# WPT_Transmitter.net
KiCad netlist of a schematic drawn in Altium Designer
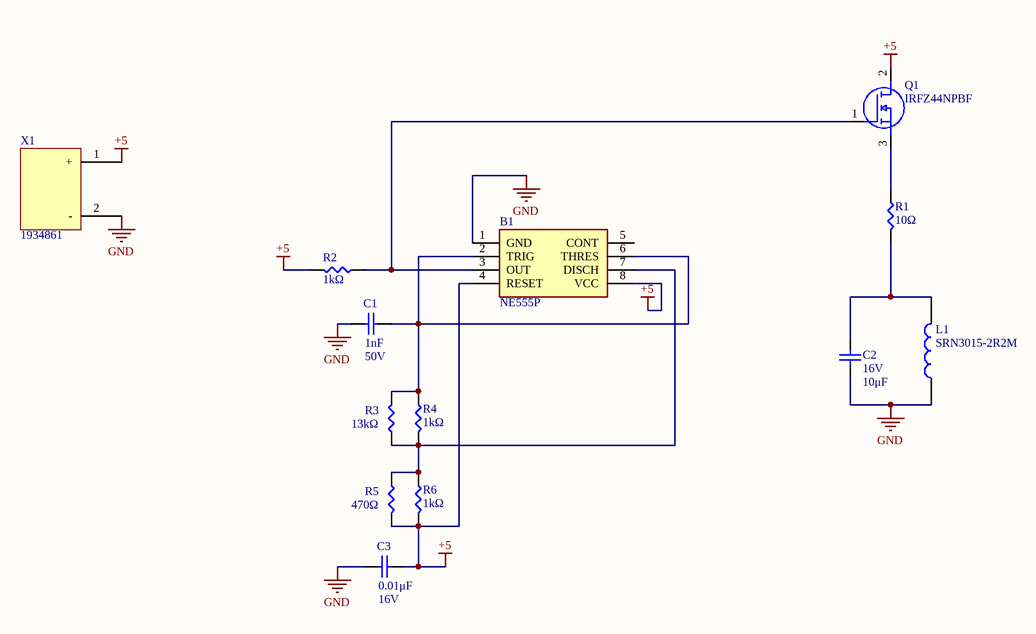
[diagram p0: WPT_Transmitter.SchDoc]

(export (version "E")
  (design (tool "Eeschema 10.0.6"))
  (components
    (comp (ref "B1")
      (value "NE555P")
      (footprint "DIP794W53P254L959H508Q8N")
      (fields (field (name "MOUSER PART NUMBER") "595-NE555P"))
      (libsource (lib "Bootcamp_Schematic_Library") (part "NE555P_1"))
    )
    (comp (ref "C1")
      (value "1nF")
      (footprint "CAP0805")
      (description "CAP CER 1000PF 50V C0G/NP0 0402")
      (fields (field (name "VOLTAGE RATING") "50V") (field (name "Comment") "GRM1555C1H102JA01D"))
      (libsource (lib "Bootcamp_Schematic_Library") (part "GRM1555C1H102JA01D"))
    )
    (comp (ref "C2")
      (value "10μF")
      (footprint "CAP0805")
      (description "CAP CER 10UF 16V X5R 0805")
      (fields (field (name "VOLTAGE RATING") "16V") (field (name "Comment") "CL21A106KOCLRNC"))
      (libsource (lib "Bootcamp_Schematic_Library") (part "CL21A106KOCLRNC"))
    )
    (comp (ref "C3")
      (value "0.01μF")
      (footprint "CAP0402")
      (description "CAP CER 10000PF 16V X7R 0402")
      (fields (field (name "VOLTAGE RATING") "16V") (field (name "Comment") "KGM05AR71C103KH"))
      (libsource (lib "Bootcamp_Schematic_Library") (part "KGM05AR71C103KH"))
    )
    (comp (ref "L1")
      (value "SRN3015-2R2M")
      (footprint "INDPM3027X150N")
      (fields (field (name "MOUSER PART NUMBER") "652-SRN3015-2R2M"))
      (libsource (lib "Bootcamp_Schematic_Library") (part "SRN3015-2R2M"))
    )
    (comp (ref "Q1")
      (value "IRFZ44NPBF")
      (footprint "TO254P483X1016X1994-3P")
      (fields (field (name "MOUSER PART NUMBER") "942-IRFZ44NPBF"))
      (libsource (lib "Bootcamp_Schematic_Library") (part "IRFZ44NPBF"))
    )
    (comp (ref "R1")
      (value "10Ω")
      (footprint "RES1206")
      (description "10 Ohms ±1% 0.5W, 1/2W Chip Resistor 1206 (3216 Metric) Anti-Sulfur Thin Film")
      (fields (field (name "Comment") "RNCP1206FTD10R0"))
      (libsource (lib "Bootcamp_Schematic_Library") (part "RNCP1206FTD10R0"))
    )
    (comp (ref "R2")
      (value "1kΩ")
      (footprint "RES1206")
      (description "RES 1K OHM 1% 1/2W 1206")
      (fields (field (name "Comment") "RNCP1206FTD1K00"))
      (libsource (lib "Bootcamp_Schematic_Library") (part "RNCP1206FTD1K00"))
    )
    (comp (ref "R3")
      (value "13kΩ")
      (footprint "RES0402")
      (description "RES 13K OHM 1% 1/16W 0402")
      (fields (field (name "Comment") "RC0402FR-0713KL"))
      (libsource (lib "Bootcamp_Schematic_Library") (part "RC0402FR-0713KL"))
    )
    (comp (ref "R4")
      (value "1kΩ")
      (footprint "RES1206")
      (description "RES 1K OHM 1% 1/2W 1206")
      (fields (field (name "Comment") "RNCP1206FTD1K00"))
      (libsource (lib "Bootcamp_Schematic_Library") (part "RNCP1206FTD1K00"))
    )
    (comp (ref "R5")
      (value "470Ω")
      (footprint "RES1206")
      (description "RES 470 OHM 1% 1/2W 1206")
      (fields (field (name "Comment") "CRGP1206F470R"))
      (libsource (lib "Bootcamp_Schematic_Library") (part "CRGP1206F470R"))
    )
    (comp (ref "R6")
      (value "1kΩ")
      (footprint "RES1206")
      (description "RES 1K OHM 1% 1/2W 1206")
      (fields (field (name "Comment") "RNCP1206FTD1K00"))
      (libsource (lib "Bootcamp_Schematic_Library") (part "RNCP1206FTD1K00"))
    )
    (comp (ref "X1")
      (value "1934861")
      (footprint "1934861")
      (libsource (lib "Bootcamp_Schematic_Library") (part "1934861"))
    )
  )
  (nets
    (net (code "1") (name "+5") (class "Default")
      (node (ref "B1") (pin "4") (pinfunction "RESET_4") (pintype "passive"))
      (node (ref "B1") (pin "8") (pinfunction "VCC_8") (pintype "passive"))
      (node (ref "C3") (pin "2") (pinfunction "2_2") (pintype "passive"))
      (node (ref "Q1") (pin "2") (pinfunction "D_2") (pintype "passive"))
      (node (ref "R2") (pin "1") (pinfunction "1_1") (pintype "passive"))
      (node (ref "R5") (pin "1") (pinfunction "1_1") (pintype "passive"))
      (node (ref "R6") (pin "1") (pinfunction "1_1") (pintype "passive"))
      (node (ref "X1") (pin "1") (pinfunction "+_1") (pintype "passive"))
    )
    (net (code "2") (name "GND") (class "Default")
      (node (ref "B1") (pin "1") (pinfunction "GND_1") (pintype "passive"))
      (node (ref "C1") (pin "1") (pinfunction "1_1") (pintype "passive"))
      (node (ref "C2") (pin "1") (pinfunction "1_1") (pintype "passive"))
      (node (ref "C3") (pin "1") (pinfunction "1_1") (pintype "passive"))
      (node (ref "L1") (pin "1") (pinfunction "1_1") (pintype "passive"))
      (node (ref "X1") (pin "2") (pinfunction "-_2") (pintype "passive"))
    )
    (net (code "3") (name "Net-(B1-DISCH)") (class "Default")
      (node (ref "B1") (pin "7") (pinfunction "DISCH_7") (pintype "passive"))
      (node (ref "R3") (pin "2") (pinfunction "2_2") (pintype "passive"))
      (node (ref "R4") (pin "1") (pinfunction "1_1") (pintype "passive"))
      (node (ref "R5") (pin "2") (pinfunction "2_2") (pintype "passive"))
      (node (ref "R6") (pin "2") (pinfunction "2_2") (pintype "passive"))
    )
    (net (code "4") (name "Net-(B1-OUT)") (class "Default")
      (node (ref "B1") (pin "3") (pinfunction "OUT_3") (pintype "passive"))
      (node (ref "Q1") (pin "1") (pinfunction "G_1") (pintype "passive"))
      (node (ref "R2") (pin "2") (pinfunction "2_2") (pintype "passive"))
    )
    (net (code "5") (name "Net-(B1-THRES)") (class "Default")
      (node (ref "B1") (pin "2") (pinfunction "TRIG_2") (pintype "passive"))
      (node (ref "B1") (pin "6") (pinfunction "THRES_6") (pintype "passive"))
      (node (ref "C1") (pin "2") (pinfunction "2_2") (pintype "passive"))
      (node (ref "R3") (pin "1") (pinfunction "1_1") (pintype "passive"))
      (node (ref "R4") (pin "2") (pinfunction "2_2") (pintype "passive"))
    )
    (net (code "6") (name "Net-(C2-Pad2)") (class "Default")
      (node (ref "C2") (pin "2") (pinfunction "2_2") (pintype "passive"))
      (node (ref "L1") (pin "2") (pinfunction "2_2") (pintype "passive"))
      (node (ref "R1") (pin "1") (pinfunction "1_1") (pintype "passive"))
    )
    (net (code "7") (name "Net-(Q1-S)") (class "Default")
      (node (ref "Q1") (pin "3") (pinfunction "S_3") (pintype "passive"))
      (node (ref "R1") (pin "2") (pinfunction "2_2") (pintype "passive"))
    )
    (net (code "8") (name "unconnected-(B1-CONT-Pad5)") (class "Default")
      (node (ref "B1") (pin "5") (pinfunction "CONT_5") (pintype "passive"))
    )
  )
)
